# user_interface.net
KiCad netlist of a schematic drawn in Altium Designer
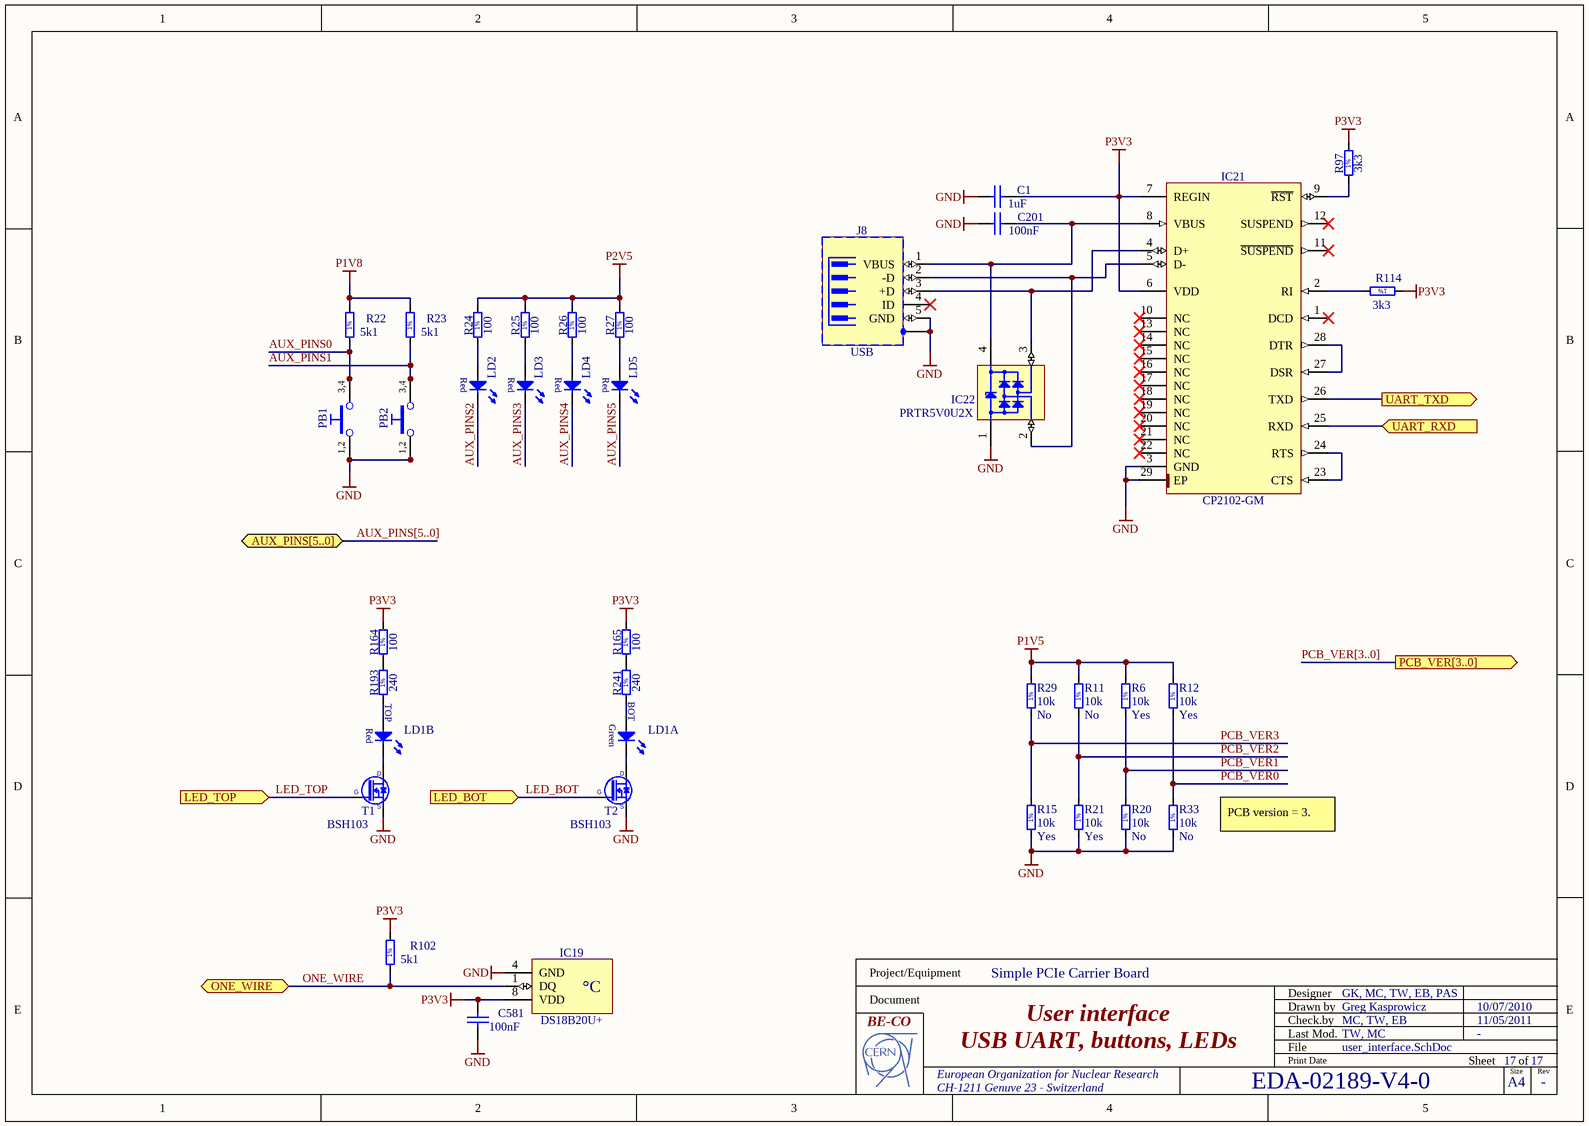
[diagram p0: user_interface.SchDoc]

(export (version "E")
  (design (tool "Eeschema 10.0.6"))
  (components
    (comp (ref "C1")
      (value "1uF")
      (footprint "CAPC1608X87N")
      (description "Non-polarised capacitor")
      (fields
        (field (name "PART NUMBER") "CC0603_1UF_16V_10%_X7R")
        (field (name "VOLTAGE") "16V")
        (field (name "AUTHOR") "CERN DEM JLC")
      )
      (libsource (lib "Capacitors") (part "Capacitor - non polarized"))
    )
    (comp (ref "C201")
      (value "100nF")
      (footprint "CAPC1608X87N")
      (description "Non-polarised capacitor")
      (fields
        (field (name "PART NUMBER") "CC0603_100NF_50V_10%_X7R")
        (field (name "VOLTAGE") "50V")
        (field (name "AUTHOR") "CERN DEM JLC")
      )
      (libsource (lib "Capacitors") (part "Capacitor - non polarized"))
    )
    (comp (ref "C581")
      (value "100nF")
      (footprint "CAPC1608X87N")
      (description "Non-polarised capacitor")
      (fields
        (field (name "PART NUMBER") "CC0603_100NF_50V_10%_X7R")
        (field (name "VOLTAGE") "50V")
        (field (name "AUTHOR") "CERN DEM JLC")
      )
      (libsource (lib "Capacitors") (part "Capacitor - non polarized"))
    )
    (comp (ref "IC19")
      (value "DS18B20U+")
      (footprint "SOP65P490X110-8N")
      (description "Programmable Resolution 1-Wire Digital Thermometer")
      (fields (field (name "MANUFACTURER") "DALLAS MAXIM") (field (name "AUTHOR") "CERN DEM JLC"))
      (libsource (lib "ICs And Semiconductors") (part "DS18B20U+"))
    )
    (comp (ref "IC21")
      (value "CP2102-GM")
      (footprint "QFN50P500X500X100-29N-S335")
      (description "Single-Chip USB to UART Bridge")
      (fields (field (name "MANUFACTURER") "SILICON LABS") (field (name "AUTHOR") "CERN DEM JLC"))
      (libsource (lib "ICs And Semiconductors") (part "CP2102-GM"))
    )
    (comp (ref "IC22")
      (value "PRTR5V0U2X")
      (footprint "SOT190P230X110-4N")
      (description "Ultra Low Capacitance Double Rail-to-Rail ESD Protection Diode")
      (fields
        (field (name "VOLTAGE") "5.5V")
        (field (name "MANUFACTURER") "PHILIPS NXP")
        (field (name "AUTHOR") "CERN DEM JLC")
      )
      (libsource (lib "ICs And Semiconductors") (part "PRTR5V0U2X"))
    )
    (comp (ref "J8")
      (value "USB")
      (footprint "TYCO_1734035-1")
      (description "5 Pin + 1 Shield USB Receptacle")
      (fields
        (field (name "PART NUMBER") "TYCO_1734035-1")
        (field (name "MANUFACTURER") "TYCO ELECTRONICS")
        (field (name "AUTHOR") "CERN DEM JLC")
      )
      (libsource (lib "Connectors") (part "Connector USB 5 Pin + 1Shield"))
    )
    (comp (ref "LD1")
      (value "Red/Green")
      (footprint "LED_DIALIGHT_571-0112F")
      (description "2x LED  Botom Green, Top Red")
      (fields
        (field (name "PART NUMBER") "LED_DIALIGHT_571-0112F")
        (field (name "MANUFACTURER") "DIALIGHT")
        (field (name "AUTHOR") "CERN DEM JLC")
      )
      (libsource (lib "ICs And Semiconductors") (part "LED x2 G-1C2A-BOT_R-3C4A-TOP"))
    )
    (comp (ref "LD2")
      (value "Red")
      (footprint "LEDC1608X80N_RED")
      (description "LED Red 1C 2A")
      (fields
        (field (name "PART NUMBER") "LED_ROHM_SML-311UTT86K")
        (field (name "MANUFACTURER") "ROHM")
        (field (name "AUTHOR") "CERN DEM JLC")
      )
      (libsource (lib "ICs And Semiconductors") (part "LED Red 1C 2A"))
    )
    (comp (ref "LD3")
      (value "Red")
      (footprint "LEDC1608X80N_RED")
      (description "LED Red 1C 2A")
      (fields
        (field (name "PART NUMBER") "LED_ROHM_SML-311UTT86K")
        (field (name "MANUFACTURER") "ROHM")
        (field (name "AUTHOR") "CERN DEM JLC")
      )
      (libsource (lib "ICs And Semiconductors") (part "LED Red 1C 2A"))
    )
    (comp (ref "LD4")
      (value "Red")
      (footprint "LEDC1608X80N_RED")
      (description "LED Red 1C 2A")
      (fields
        (field (name "PART NUMBER") "LED_ROHM_SML-311UTT86K")
        (field (name "MANUFACTURER") "ROHM")
        (field (name "AUTHOR") "CERN DEM JLC")
      )
      (libsource (lib "ICs And Semiconductors") (part "LED Red 1C 2A"))
    )
    (comp (ref "LD5")
      (value "Red")
      (footprint "LEDC1608X80N_RED")
      (description "LED Red 1C 2A")
      (fields
        (field (name "PART NUMBER") "LED_ROHM_SML-311UTT86K")
        (field (name "MANUFACTURER") "ROHM")
        (field (name "AUTHOR") "CERN DEM JLC")
      )
      (libsource (lib "ICs And Semiconductors") (part "LED Red 1C 2A"))
    )
    (comp (ref "PB1")
      (value "Push Button")
      (footprint "PB_TYCO_ALCOSWITCH_FSM2JSMA")
      (description "Push-Button Switch SPDT")
      (fields
        (field (name "PART NUMBER") "PB_TYCO_ALCOSWITCH_FSM2JSMA")
        (field (name "MANUFACTURER") "TYCO ALCOSWITCH")
        (field (name "AUTHOR") "CERN DEM JLC")
      )
      (libsource (lib "Eletro-mechanical") (part "PB SPST 12NO-34NO"))
    )
    (comp (ref "PB2")
      (value "Push Button")
      (footprint "PB_TYCO_ALCOSWITCH_FSM2JSMA")
      (description "Push-Button Switch SPDT")
      (fields
        (field (name "PART NUMBER") "PB_TYCO_ALCOSWITCH_FSM2JSMA")
        (field (name "MANUFACTURER") "TYCO ALCOSWITCH")
        (field (name "AUTHOR") "CERN DEM JLC")
      )
      (libsource (lib "Eletro-mechanical") (part "PB SPST 12NO-34NO"))
    )
    (comp (ref "R6")
      (value "10k")
      (footprint "RESC1608X55N")
      (description "Resistor - 1%")
      (fields
        (field (name "PART NUMBER") "R0603_10K_1%_0.1W_100PPM")
        (field (name "POWER") "0.1W")
        (field (name "MOUNTED") "Yes")
        (field (name "AUTHOR") "CERN DEM JLC")
      )
      (libsource (lib "Resistors") (part "Resistor - 1%"))
    )
    (comp (ref "R11")
      (value "10k")
      (footprint "RESC1608X55N")
      (description "Resistor - 1%")
      (fields
        (field (name "PART NUMBER") "R0603_10K_1%_0.1W_100PPM")
        (field (name "POWER") "0.1W")
        (field (name "MOUNTED") "No")
        (field (name "AUTHOR") "CERN DEM JLC")
      )
      (libsource (lib "Resistors") (part "Resistor - 1%"))
    )
    (comp (ref "R12")
      (value "10k")
      (footprint "RESC1608X55N")
      (description "Resistor - 1%")
      (fields
        (field (name "PART NUMBER") "R0603_10K_1%_0.1W_100PPM")
        (field (name "POWER") "0.1W")
        (field (name "MOUNTED") "Yes")
        (field (name "AUTHOR") "CERN DEM JLC")
      )
      (libsource (lib "Resistors") (part "Resistor - 1%"))
    )
    (comp (ref "R15")
      (value "10k")
      (footprint "RESC1608X55N")
      (description "Resistor - 1%")
      (fields
        (field (name "PART NUMBER") "R0603_10K_1%_0.1W_100PPM")
        (field (name "POWER") "0.1W")
        (field (name "MOUNTED") "Yes")
        (field (name "AUTHOR") "CERN DEM JLC")
      )
      (libsource (lib "Resistors") (part "Resistor - 1%"))
    )
    (comp (ref "R20")
      (value "10k")
      (footprint "RESC1608X55N")
      (description "Resistor - 1%")
      (fields
        (field (name "PART NUMBER") "R0603_10K_1%_0.1W_100PPM")
        (field (name "POWER") "0.1W")
        (field (name "MOUNTED") "No")
        (field (name "AUTHOR") "CERN DEM JLC")
      )
      (libsource (lib "Resistors") (part "Resistor - 1%"))
    )
    (comp (ref "R21")
      (value "10k")
      (footprint "RESC1608X55N")
      (description "Resistor - 1%")
      (fields
        (field (name "PART NUMBER") "R0603_10K_1%_0.1W_100PPM")
        (field (name "POWER") "0.1W")
        (field (name "MOUNTED") "Yes")
        (field (name "AUTHOR") "CERN DEM JLC")
      )
      (libsource (lib "Resistors") (part "Resistor - 1%"))
    )
    (comp (ref "R22")
      (value "5k1")
      (footprint "RESC1608X55N")
      (description "Resistor - 1%")
      (fields
        (field (name "PART NUMBER") "R0603_5K1_1%_0.1W_100PPM")
        (field (name "POWER") "0.1W")
        (field (name "AUTHOR") "CERN DEM JLC")
      )
      (libsource (lib "Resistors") (part "Resistor - 1%"))
    )
    (comp (ref "R23")
      (value "5k1")
      (footprint "RESC1608X55N")
      (description "Resistor - 1%")
      (fields
        (field (name "PART NUMBER") "R0603_5K1_1%_0.1W_100PPM")
        (field (name "POWER") "0.1W")
        (field (name "AUTHOR") "CERN DEM JLC")
      )
      (libsource (lib "Resistors") (part "Resistor - 1%"))
    )
    (comp (ref "R24")
      (value "100")
      (footprint "RESC1608X55N")
      (description "Resistor - 1%")
      (fields
        (field (name "PART NUMBER") "R0603_100R_1%_0.1W_100PPM")
        (field (name "POWER") "0.1W")
        (field (name "AUTHOR") "CERN DEM JLC")
      )
      (libsource (lib "Resistors") (part "Resistor - 1%"))
    )
    (comp (ref "R25")
      (value "100")
      (footprint "RESC1608X55N")
      (description "Resistor - 1%")
      (fields
        (field (name "PART NUMBER") "R0603_100R_1%_0.1W_100PPM")
        (field (name "POWER") "0.1W")
        (field (name "AUTHOR") "CERN DEM JLC")
      )
      (libsource (lib "Resistors") (part "Resistor - 1%"))
    )
    (comp (ref "R26")
      (value "100")
      (footprint "RESC1608X55N")
      (description "Resistor - 1%")
      (fields
        (field (name "PART NUMBER") "R0603_100R_1%_0.1W_100PPM")
        (field (name "POWER") "0.1W")
        (field (name "AUTHOR") "CERN DEM JLC")
      )
      (libsource (lib "Resistors") (part "Resistor - 1%"))
    )
    (comp (ref "R27")
      (value "100")
      (footprint "RESC1608X55N")
      (description "Resistor - 1%")
      (fields
        (field (name "PART NUMBER") "R0603_100R_1%_0.1W_100PPM")
        (field (name "POWER") "0.1W")
        (field (name "AUTHOR") "CERN DEM JLC")
      )
      (libsource (lib "Resistors") (part "Resistor - 1%"))
    )
    (comp (ref "R29")
      (value "10k")
      (footprint "RESC1608X55N")
      (description "Resistor - 1%")
      (fields
        (field (name "PART NUMBER") "R0603_10K_1%_0.1W_100PPM")
        (field (name "POWER") "0.1W")
        (field (name "MOUNTED") "No")
        (field (name "AUTHOR") "CERN DEM JLC")
      )
      (libsource (lib "Resistors") (part "Resistor - 1%"))
    )
    (comp (ref "R33")
      (value "10k")
      (footprint "RESC1608X55N")
      (description "Resistor - 1%")
      (fields
        (field (name "PART NUMBER") "R0603_10K_1%_0.1W_100PPM")
        (field (name "POWER") "0.1W")
        (field (name "MOUNTED") "No")
        (field (name "AUTHOR") "CERN DEM JLC")
      )
      (libsource (lib "Resistors") (part "Resistor - 1%"))
    )
    (comp (ref "R97")
      (value "3k3")
      (footprint "RESC1608X55N")
      (description "Resistor - 1%")
      (fields
        (field (name "PART NUMBER") "R0603_3K3_1%_0.1W_100PPM")
        (field (name "POWER") "0.1W")
        (field (name "AUTHOR") "CERN DEM JLC")
      )
      (libsource (lib "Resistors") (part "Resistor - 1%"))
    )
    (comp (ref "R102")
      (value "5k1")
      (footprint "RESC1608X55N")
      (description "Resistor - 1%")
      (fields
        (field (name "PART NUMBER") "R0603_5K1_1%_0.1W_100PPM")
        (field (name "POWER") "0.1W")
        (field (name "AUTHOR") "CERN DEM JLC")
      )
      (libsource (lib "Resistors") (part "Resistor - 1%"))
    )
    (comp (ref "R114")
      (value "3k3")
      (footprint "RESC1608X55N")
      (description "Resistor - 1%")
      (fields
        (field (name "PART NUMBER") "R0603_3K3_1%_0.1W_100PPM")
        (field (name "POWER") "0.1W")
        (field (name "AUTHOR") "CERN DEM JLC")
      )
      (libsource (lib "Resistors") (part "Resistor - 1%"))
    )
    (comp (ref "R164")
      (value "100")
      (footprint "RESC1608X55N")
      (description "Resistor - 1%")
      (fields
        (field (name "PART NUMBER") "R0603_100R_1%_0.1W_100PPM")
        (field (name "POWER") "0.1W")
        (field (name "AUTHOR") "CERN DEM JLC")
      )
      (libsource (lib "Resistors") (part "Resistor - 1%"))
    )
    (comp (ref "R165")
      (value "100")
      (footprint "RESC1608X55N")
      (description "Resistor - 1%")
      (fields
        (field (name "PART NUMBER") "R0603_100R_1%_0.1W_100PPM")
        (field (name "POWER") "0.1W")
        (field (name "AUTHOR") "CERN DEM JLC")
      )
      (libsource (lib "Resistors") (part "Resistor - 1%"))
    )
    (comp (ref "R193")
      (value "240")
      (footprint "RESC1608X55N")
      (description "Resistor - 1%")
      (fields
        (field (name "PART NUMBER") "R0603_240R_1%_0.1W_100PPM")
        (field (name "POWER") "0.1W")
        (field (name "AUTHOR") "CERN DEM JLC")
      )
      (libsource (lib "Resistors") (part "Resistor - 1%"))
    )
    (comp (ref "R241")
      (value "240")
      (footprint "RESC1608X55N")
      (description "Resistor - 1%")
      (fields
        (field (name "PART NUMBER") "R0603_240R_1%_0.1W_100PPM")
        (field (name "POWER") "0.1W")
        (field (name "AUTHOR") "CERN DEM JLC")
      )
      (libsource (lib "Resistors") (part "Resistor - 1%"))
    )
    (comp (ref "T1")
      (value "BSH103")
      (footprint "SOT95P230X110-3N")
      (description "N-CHANNEL MOSFET WITH DIODE")
      (fields (field (name "MANUFACTURER") "NXP SEMICONDUCTORS") (field (name "AUTHOR") "CERN DEM JLC"))
      (libsource (lib "ICs And Semiconductors") (part "N-MOSFET-D 1G 2S 3D"))
    )
    (comp (ref "T2")
      (value "BSH103")
      (footprint "SOT95P230X110-3N")
      (description "N-CHANNEL MOSFET WITH DIODE")
      (fields (field (name "MANUFACTURER") "NXP SEMICONDUCTORS") (field (name "AUTHOR") "CERN DEM JLC"))
      (libsource (lib "ICs And Semiconductors") (part "N-MOSFET-D 1G 2S 3D"))
    )
  )
  (nets
    (net (code "1") (name "/AUX_PINS0") (class "Default")
      (node (ref "PB1") (pin "3") (pinfunction "3_3") (pintype "passive"))
      (node (ref "PB1") (pin "4") (pinfunction "4_4") (pintype "passive"))
      (node (ref "R22") (pin "1") (pinfunction "1_1") (pintype "passive"))
    )
    (net (code "2") (name "/AUX_PINS1") (class "Default")
      (node (ref "PB2") (pin "3") (pinfunction "3_3") (pintype "passive"))
      (node (ref "PB2") (pin "4") (pinfunction "4_4") (pintype "passive"))
      (node (ref "R23") (pin "1") (pinfunction "1_1") (pintype "passive"))
    )
    (net (code "3") (name "/AUX_PINS2") (class "Default")
      (node (ref "LD2") (pin "1") (pinfunction "C_1") (pintype "passive"))
    )
    (net (code "4") (name "/AUX_PINS3") (class "Default")
      (node (ref "LD3") (pin "1") (pinfunction "C_1") (pintype "passive"))
    )
    (net (code "5") (name "/AUX_PINS4") (class "Default")
      (node (ref "LD4") (pin "1") (pinfunction "C_1") (pintype "passive"))
    )
    (net (code "6") (name "/AUX_PINS5") (class "Default")
      (node (ref "LD5") (pin "1") (pinfunction "C_1") (pintype "passive"))
    )
    (net (code "8") (name "/LED_BOT") (class "Default")
      (node (ref "T2") (pin "1") (pinfunction "G_1") (pintype "passive"))
    )
    (net (code "9") (name "/LED_TOP") (class "Default")
      (node (ref "T1") (pin "1") (pinfunction "G_1") (pintype "passive"))
    )
    (net (code "10") (name "/ONE_WIRE") (class "Default")
      (node (ref "IC19") (pin "1") (pinfunction "DQ_1") (pintype "bidirectional"))
      (node (ref "R102") (pin "1") (pinfunction "1_1") (pintype "passive"))
    )
    (net (code "11") (name "/PCB_VER0") (class "Default")
      (node (ref "R12") (pin "1") (pinfunction "1_1") (pintype "passive"))
      (node (ref "R33") (pin "2") (pinfunction "2_2") (pintype "passive"))
    )
    (net (code "12") (name "/PCB_VER1") (class "Default")
      (node (ref "R20") (pin "2") (pinfunction "2_2") (pintype "passive"))
      (node (ref "R6") (pin "1") (pinfunction "1_1") (pintype "passive"))
    )
    (net (code "13") (name "/PCB_VER2") (class "Default")
      (node (ref "R11") (pin "1") (pinfunction "1_1") (pintype "passive"))
      (node (ref "R21") (pin "2") (pinfunction "2_2") (pintype "passive"))
    )
    (net (code "14") (name "/PCB_VER3") (class "Default")
      (node (ref "R15") (pin "2") (pinfunction "2_2") (pintype "passive"))
      (node (ref "R29") (pin "1") (pinfunction "1_1") (pintype "passive"))
    )
    (net (code "16") (name "/UART_RXD") (class "Default")
      (node (ref "IC21") (pin "25") (pinfunction "RXD_25") (pintype "input"))
    )
    (net (code "17") (name "/UART_TXD") (class "Default")
      (node (ref "IC21") (pin "26") (pinfunction "TXD_26") (pintype "output"))
    )
    (net (code "18") (name "GND") (class "Default")
      (node (ref "C1") (pin "2") (pinfunction "2_2") (pintype "passive"))
      (node (ref "C201") (pin "2") (pinfunction "2_2") (pintype "passive"))
      (node (ref "C581") (pin "2") (pinfunction "2_2") (pintype "passive"))
      (node (ref "IC19") (pin "4") (pinfunction "GND_4") (pintype "power_in"))
      (node (ref "IC21") (pin "29") (pinfunction "EP_29") (pintype "power_in"))
      (node (ref "IC21") (pin "3") (pinfunction "GND_3") (pintype "power_in"))
      (node (ref "IC22") (pin "1") (pinfunction "GND_1") (pintype "power_in"))
      (node (ref "J8") (pin "5") (pinfunction "GND_5") (pintype "bidirectional"))
      (node (ref "J8") (pin "6") (pinfunction "SH_6") (pintype "power_in"))
      (node (ref "PB1") (pin "1") (pinfunction "1_1") (pintype "passive"))
      (node (ref "PB1") (pin "2") (pinfunction "2_2") (pintype "passive"))
      (node (ref "PB2") (pin "1") (pinfunction "1_1") (pintype "passive"))
      (node (ref "PB2") (pin "2") (pinfunction "2_2") (pintype "passive"))
      (node (ref "R15") (pin "1") (pinfunction "1_1") (pintype "passive"))
      (node (ref "R20") (pin "1") (pinfunction "1_1") (pintype "passive"))
      (node (ref "R21") (pin "1") (pinfunction "1_1") (pintype "passive"))
      (node (ref "R33") (pin "1") (pinfunction "1_1") (pintype "passive"))
      (node (ref "T1") (pin "2") (pinfunction "S_2") (pintype "passive"))
      (node (ref "T2") (pin "2") (pinfunction "S_2") (pintype "passive"))
    )
    (net (code "19") (name "Net-(IC21-CTS)") (class "Default")
      (node (ref "IC21") (pin "23") (pinfunction "CTS_23") (pintype "input"))
      (node (ref "IC21") (pin "24") (pinfunction "RTS_24") (pintype "output"))
    )
    (net (code "20") (name "Net-(IC21-D+)") (class "Default")
      (node (ref "IC21") (pin "4") (pinfunction "D+_4") (pintype "bidirectional"))
      (node (ref "IC22") (pin "3") (pinfunction "I/O2_3") (pintype "bidirectional"))
      (node (ref "J8") (pin "3") (pinfunction "+D_3") (pintype "bidirectional"))
    )
    (net (code "21") (name "Net-(IC21-D-)") (class "Default")
      (node (ref "IC21") (pin "5") (pinfunction "D-_5") (pintype "bidirectional"))
      (node (ref "IC22") (pin "2") (pinfunction "I/O1_2") (pintype "bidirectional"))
      (node (ref "J8") (pin "2") (pinfunction "-D_2") (pintype "bidirectional"))
    )
    (net (code "22") (name "Net-(IC21-DSR)") (class "Default")
      (node (ref "IC21") (pin "27") (pinfunction "DSR_27") (pintype "input"))
      (node (ref "IC21") (pin "28") (pinfunction "DTR_28") (pintype "output"))
    )
    (net (code "23") (name "Net-(IC21-RI)") (class "Default")
      (node (ref "IC21") (pin "2") (pinfunction "RI_2") (pintype "input"))
      (node (ref "R114") (pin "2") (pinfunction "2_2") (pintype "passive"))
    )
    (net (code "24") (name "Net-(IC21-VBUS)") (class "Default")
      (node (ref "C201") (pin "1") (pinfunction "1_1") (pintype "passive"))
      (node (ref "IC21") (pin "8") (pinfunction "VBUS_8") (pintype "input"))
      (node (ref "IC22") (pin "4") (pinfunction "VCC_4") (pintype "power_in"))
      (node (ref "J8") (pin "1") (pinfunction "VBUS_1") (pintype "bidirectional"))
    )
    (net (code "25") (name "Net-(IC21-~{RST})") (class "Default")
      (node (ref "IC21") (pin "9") (pinfunction "~{RST}_9") (pintype "bidirectional"))
      (node (ref "R97") (pin "1") (pinfunction "1_1") (pintype "passive"))
    )
    (net (code "26") (name "Net-(LD1A-A)") (class "Default")
      (node (ref "LD1") (pin "2") (pinfunction "A_2") (pintype "passive"))
      (node (ref "R241") (pin "1") (pinfunction "1_1") (pintype "passive"))
    )
    (net (code "27") (name "Net-(LD1A-C)") (class "Default")
      (node (ref "LD1") (pin "1") (pinfunction "C_1") (pintype "passive"))
      (node (ref "T2") (pin "3") (pinfunction "D_3") (pintype "passive"))
    )
    (net (code "28") (name "Net-(LD1B-A)") (class "Default")
      (node (ref "LD1") (pin "4") (pinfunction "A_4") (pintype "passive"))
      (node (ref "R193") (pin "1") (pinfunction "1_1") (pintype "passive"))
    )
    (net (code "29") (name "Net-(LD1B-C)") (class "Default")
      (node (ref "LD1") (pin "3") (pinfunction "C_3") (pintype "passive"))
      (node (ref "T1") (pin "3") (pinfunction "D_3") (pintype "passive"))
    )
    (net (code "30") (name "Net-(LD2-A)") (class "Default")
      (node (ref "LD2") (pin "2") (pinfunction "A_2") (pintype "passive"))
      (node (ref "R24") (pin "1") (pinfunction "1_1") (pintype "passive"))
    )
    (net (code "31") (name "Net-(LD3-A)") (class "Default")
      (node (ref "LD3") (pin "2") (pinfunction "A_2") (pintype "passive"))
      (node (ref "R25") (pin "1") (pinfunction "1_1") (pintype "passive"))
    )
    (net (code "32") (name "Net-(LD4-A)") (class "Default")
      (node (ref "LD4") (pin "2") (pinfunction "A_2") (pintype "passive"))
      (node (ref "R26") (pin "1") (pinfunction "1_1") (pintype "passive"))
    )
    (net (code "33") (name "Net-(LD5-A)") (class "Default")
      (node (ref "LD5") (pin "2") (pinfunction "A_2") (pintype "passive"))
      (node (ref "R27") (pin "1") (pinfunction "1_1") (pintype "passive"))
    )
    (net (code "34") (name "Net-(R164-Pad1)") (class "Default")
      (node (ref "R164") (pin "1") (pinfunction "1_1") (pintype "passive"))
      (node (ref "R193") (pin "2") (pinfunction "2_2") (pintype "passive"))
    )
    (net (code "35") (name "Net-(R165-Pad1)") (class "Default")
      (node (ref "R165") (pin "1") (pinfunction "1_1") (pintype "passive"))
      (node (ref "R241") (pin "2") (pinfunction "2_2") (pintype "passive"))
    )
    (net (code "36") (name "P1V5") (class "Default")
      (node (ref "R11") (pin "2") (pinfunction "2_2") (pintype "passive"))
      (node (ref "R12") (pin "2") (pinfunction "2_2") (pintype "passive"))
      (node (ref "R29") (pin "2") (pinfunction "2_2") (pintype "passive"))
      (node (ref "R6") (pin "2") (pinfunction "2_2") (pintype "passive"))
    )
    (net (code "37") (name "P1V8") (class "Default")
      (node (ref "R22") (pin "2") (pinfunction "2_2") (pintype "passive"))
      (node (ref "R23") (pin "2") (pinfunction "2_2") (pintype "passive"))
    )
    (net (code "38") (name "P2V5") (class "Default")
      (node (ref "R24") (pin "2") (pinfunction "2_2") (pintype "passive"))
      (node (ref "R25") (pin "2") (pinfunction "2_2") (pintype "passive"))
      (node (ref "R26") (pin "2") (pinfunction "2_2") (pintype "passive"))
      (node (ref "R27") (pin "2") (pinfunction "2_2") (pintype "passive"))
    )
    (net (code "39") (name "P3V3") (class "Default")
      (node (ref "C1") (pin "1") (pinfunction "1_1") (pintype "passive"))
      (node (ref "C581") (pin "1") (pinfunction "1_1") (pintype "passive"))
      (node (ref "IC19") (pin "8") (pinfunction "VDD_8") (pintype "power_in"))
      (node (ref "IC21") (pin "6") (pinfunction "VDD_6") (pintype "power_in"))
      (node (ref "IC21") (pin "7") (pinfunction "REGIN_7") (pintype "power_in"))
      (node (ref "R102") (pin "2") (pinfunction "2_2") (pintype "passive"))
      (node (ref "R114") (pin "1") (pinfunction "1_1") (pintype "passive"))
      (node (ref "R164") (pin "2") (pinfunction "2_2") (pintype "passive"))
      (node (ref "R165") (pin "2") (pinfunction "2_2") (pintype "passive"))
      (node (ref "R97") (pin "2") (pinfunction "2_2") (pintype "passive"))
    )
    (net (code "40") (name "unconnected-(IC21-DCD-Pad1)") (class "Default")
      (node (ref "IC21") (pin "1") (pinfunction "DCD_1") (pintype "input+no_connect"))
    )
    (net (code "41") (name "unconnected-(IC21-NC-Pad10)") (class "Default")
      (node (ref "IC21") (pin "10") (pinfunction "NC_10") (pintype "passive+no_connect"))
    )
    (net (code "42") (name "unconnected-(IC21-NC-Pad13)") (class "Default")
      (node (ref "IC21") (pin "13") (pinfunction "NC_13") (pintype "passive+no_connect"))
    )
    (net (code "43") (name "unconnected-(IC21-NC-Pad14)") (class "Default")
      (node (ref "IC21") (pin "14") (pinfunction "NC_14") (pintype "passive+no_connect"))
    )
    (net (code "44") (name "unconnected-(IC21-NC-Pad15)") (class "Default")
      (node (ref "IC21") (pin "15") (pinfunction "NC_15") (pintype "passive+no_connect"))
    )
    (net (code "45") (name "unconnected-(IC21-NC-Pad16)") (class "Default")
      (node (ref "IC21") (pin "16") (pinfunction "NC_16") (pintype "passive+no_connect"))
    )
    (net (code "46") (name "unconnected-(IC21-NC-Pad17)") (class "Default")
      (node (ref "IC21") (pin "17") (pinfunction "NC_17") (pintype "passive+no_connect"))
    )
    (net (code "47") (name "unconnected-(IC21-NC-Pad18)") (class "Default")
      (node (ref "IC21") (pin "18") (pinfunction "NC_18") (pintype "passive+no_connect"))
    )
    (net (code "48") (name "unconnected-(IC21-NC-Pad19)") (class "Default")
      (node (ref "IC21") (pin "19") (pinfunction "NC_19") (pintype "passive+no_connect"))
    )
    (net (code "49") (name "unconnected-(IC21-NC-Pad20)") (class "Default")
      (node (ref "IC21") (pin "20") (pinfunction "NC_20") (pintype "passive+no_connect"))
    )
    (net (code "50") (name "unconnected-(IC21-NC-Pad21)") (class "Default")
      (node (ref "IC21") (pin "21") (pinfunction "NC_21") (pintype "passive+no_connect"))
    )
    (net (code "51") (name "unconnected-(IC21-NC-Pad22)") (class "Default")
      (node (ref "IC21") (pin "22") (pinfunction "NC_22") (pintype "passive+no_connect"))
    )
    (net (code "52") (name "unconnected-(IC21-SUSPEND-Pad12)") (class "Default")
      (node (ref "IC21") (pin "12") (pinfunction "SUSPEND_12") (pintype "output+no_connect"))
    )
    (net (code "53") (name "unconnected-(IC21-~{SUSPEND}-Pad11)") (class "Default")
      (node (ref "IC21") (pin "11") (pinfunction "~{SUSPEND}_11") (pintype "output+no_connect"))
    )
    (net (code "54") (name "unconnected-(J8-ID-Pad4)") (class "Default")
      (node (ref "J8") (pin "4") (pinfunction "ID_4") (pintype "passive+no_connect"))
    )
  )
)
